# AMG8833convert.net
KiCad netlist of a schematic drawn in Altium Designer
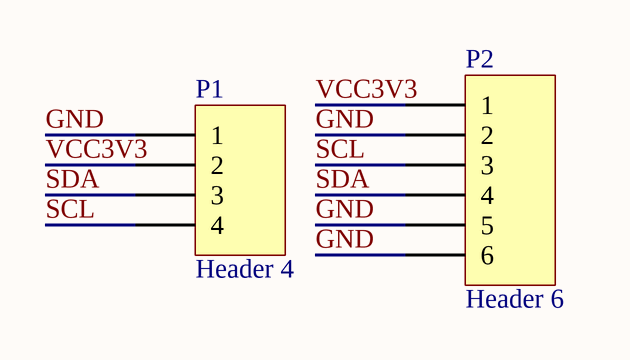
[diagram p0: AMG8833convert.SchDoc]

(export (version "E")
  (design (tool "Eeschema 10.0.6"))
  (components
    (comp (ref "P1")
      (value "Header 4")
      (footprint "HDR1X4")
      (description "Header, 4-Pin")
      (fields (field (name "PUBLISHER") "Altium Limited"))
      (libsource (lib "Miscellaneous Connectors") (part "Header 4"))
    )
    (comp (ref "P2")
      (value "Header 6")
      (footprint "HDR1X6")
      (description "Header, 6-Pin")
      (fields (field (name "PUBLISHER") "Altium Limited"))
      (libsource (lib "Miscellaneous Connectors") (part "Header 6"))
    )
  )
  (nets
    (net (code "1") (name "/GND") (class "Default")
      (node (ref "P1") (pin "1") (pinfunction "1_1") (pintype "passive"))
      (node (ref "P2") (pin "2") (pinfunction "2_2") (pintype "passive"))
      (node (ref "P2") (pin "5") (pinfunction "5_5") (pintype "passive"))
      (node (ref "P2") (pin "6") (pinfunction "6_6") (pintype "passive"))
    )
    (net (code "2") (name "/SCL") (class "Default")
      (node (ref "P1") (pin "4") (pinfunction "4_4") (pintype "passive"))
      (node (ref "P2") (pin "3") (pinfunction "3_3") (pintype "passive"))
    )
    (net (code "3") (name "/SDA") (class "Default")
      (node (ref "P1") (pin "3") (pinfunction "3_3") (pintype "passive"))
      (node (ref "P2") (pin "4") (pinfunction "4_4") (pintype "passive"))
    )
    (net (code "4") (name "/VCC3V3") (class "Default")
      (node (ref "P1") (pin "2") (pinfunction "2_2") (pintype "passive"))
      (node (ref "P2") (pin "1") (pinfunction "1_1") (pintype "passive"))
    )
  )
)
